# Awesome-Shield-1_0.net
KiCad netlist of a schematic drawn in EAGLE
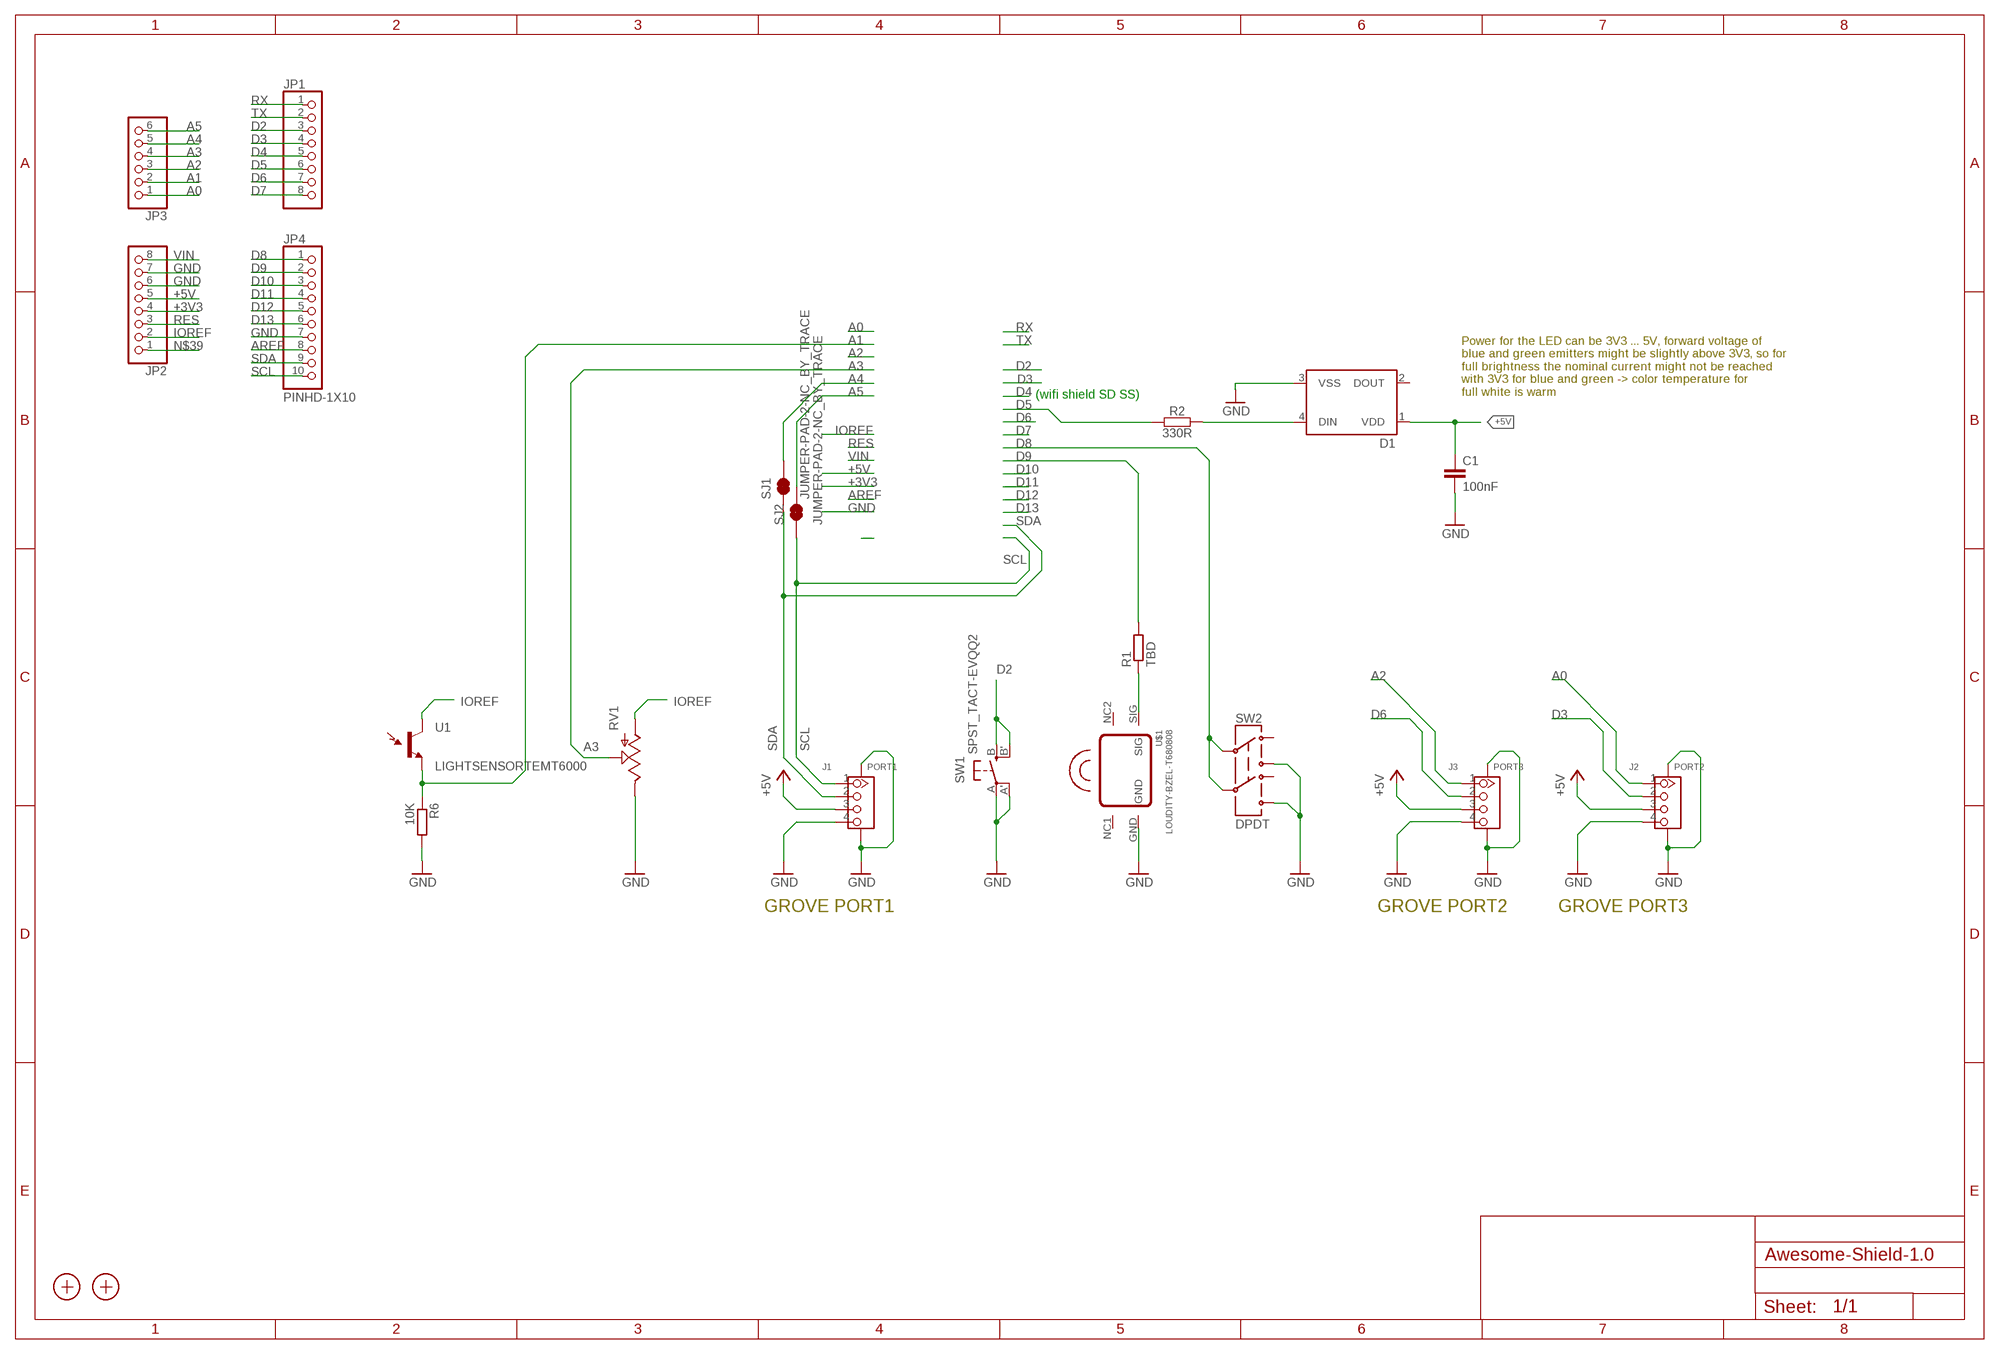
[diagram p0: schematic, sheet 1]

(export (version "E")
  (design (tool "Eeschema 10.0.6"))
  (components
    (comp (ref "C1")
      (value "100nF")
      (footprint "eagle-import:C0603")
      (libsource (lib "eagle-import") (part "C-EUC0603"))
    )
    (comp (ref "D1")
      (value "WS2812B")
      (footprint "eagle-import:WS2812B")
      (libsource (lib "eagle-import") (part "WS2812B"))
    )
    (comp (ref "J1")
      (value "PORT1")
      (footprint "eagle-import:HW4-SMD-2.0")
      (libsource (lib "eagle-import") (part "GROVE-CONNECTOR-SMD(4+2P-2.0)"))
    )
    (comp (ref "J2")
      (value "PORT2")
      (footprint "eagle-import:HW4-SMD-2.0")
      (libsource (lib "eagle-import") (part "GROVE-CONNECTOR-SMD(4+2P-2.0)"))
    )
    (comp (ref "J3")
      (value "PORT3")
      (footprint "eagle-import:HW4-SMD-2.0")
      (libsource (lib "eagle-import") (part "GROVE-CONNECTOR-SMD(4+2P-2.0)"))
    )
    (comp (ref "JP1")
      (value "PINHD-1X8CLEANBIG")
      (footprint "eagle-import:1X08-CLEANBIG")
      (libsource (lib "eagle-import") (part "PINHD-1X8CLEANBIG"))
    )
    (comp (ref "JP2")
      (value "PINHD-1X8CLEANBIG")
      (footprint "eagle-import:1X08-CLEANBIG")
      (libsource (lib "eagle-import") (part "PINHD-1X8CLEANBIG"))
    )
    (comp (ref "JP3")
      (value "PINHD-1X6CLEAN")
      (footprint "eagle-import:1X06-CLEAN")
      (libsource (lib "eagle-import") (part "PINHD-1X6CLEAN"))
    )
    (comp (ref "JP4")
      (value "PINHD-1X10")
      (footprint "eagle-import:1X10-BIG")
      (libsource (lib "eagle-import") (part "PINHD-1X10"))
    )
    (comp (ref "R1")
      (value "TBD")
      (footprint "eagle-import:R1206")
      (libsource (lib "eagle-import") (part "R-EU_R1206"))
    )
    (comp (ref "R2")
      (value "330R")
      (footprint "eagle-import:C1206")
      (libsource (lib "eagle-import") (part "RESISTOR-1206"))
    )
    (comp (ref "R6")
      (value "10K")
      (footprint "eagle-import:R1206")
      (libsource (lib "eagle-import") (part "R-EU_R1206"))
    )
    (comp (ref "RV1")
      (value "POT")
      (footprint "eagle-import:ALPS_POT")
      (libsource (lib "eagle-import") (part "POT"))
    )
    (comp (ref "SJ1")
      (value "JUMPER-PAD-2-NC_BY_TRACE")
      (footprint "eagle-import:PAD-JUMPER-2-NC_BY_TRACE_YES_SILK")
      (libsource (lib "eagle-import") (part "JUMPER-PAD-2-NC_BY_TRACE"))
    )
    (comp (ref "SJ2")
      (value "JUMPER-PAD-2-NC_BY_TRACE")
      (footprint "eagle-import:PAD-JUMPER-2-NC_BY_TRACE_YES_SILK")
      (libsource (lib "eagle-import") (part "JUMPER-PAD-2-NC_BY_TRACE"))
    )
    (comp (ref "SW1")
      (value "SPST_TACT-EVQQ2")
      (footprint "eagle-import:EVQ-Q2")
      (libsource (lib "eagle-import") (part "SPST_TACT-EVQQ2"))
    )
    (comp (ref "SW2")
      (value "DPDT")
      (footprint "eagle-import:AYZ0202")
      (libsource (lib "eagle-import") (part "SWITCH-DPDTAYZ0202"))
    )
    (comp (ref "U$1")
      (value "LOUDITY-BZEL-T680808")
      (footprint "eagle-import:SMT-68")
      (libsource (lib "eagle-import") (part "LOUDITY-BZEL-T680808"))
    )
    (comp (ref "U1")
      (value "LIGHTSENSORTEMT6000")
      (footprint "eagle-import:TEMT6000-SEN")
      (libsource (lib "eagle-import") (part "LIGHTSENSORTEMT6000"))
    )
    (comp (ref "X1")
      (value "PASSER-07")
      (footprint "eagle-import:PASSER_07MM")
      (libsource (lib "eagle-import") (part "PASSER-07"))
    )
    (comp (ref "X2")
      (value "PASSER-07")
      (footprint "eagle-import:PASSER_07MM")
      (libsource (lib "eagle-import") (part "PASSER-07"))
    )
  )
  (nets
    (net (code "1") (name "+5V") (class "Default")
      (node (ref "C1") (pin "1") (pinfunction "1_1") (pintype "passive"))
      (node (ref "D1") (pin "1") (pinfunction "VDD_1") (pintype "power_in"))
      (node (ref "J1") (pin "3") (pinfunction "3_3") (pintype "bidirectional"))
      (node (ref "J2") (pin "3") (pinfunction "3_3") (pintype "bidirectional"))
      (node (ref "J3") (pin "3") (pinfunction "3_3") (pintype "bidirectional"))
      (node (ref "JP2") (pin "5") (pinfunction "5_5") (pintype "passive"))
    )
    (net (code "2") (name "/+3V3") (class "Default")
      (node (ref "JP2") (pin "4") (pinfunction "4_4") (pintype "passive"))
    )
    (net (code "3") (name "/A0") (class "Default")
      (node (ref "J2") (pin "1") (pinfunction "1_1") (pintype "bidirectional"))
      (node (ref "JP3") (pin "1") (pinfunction "1_1") (pintype "passive"))
    )
    (net (code "4") (name "/A1") (class "Default")
      (node (ref "JP3") (pin "2") (pinfunction "2_2") (pintype "passive"))
      (node (ref "R6") (pin "1") (pinfunction "1_1") (pintype "passive"))
      (node (ref "U1") (pin "EMITTER") (pinfunction "E1_EMITTER") (pintype "passive"))
    )
    (net (code "5") (name "/A2") (class "Default")
      (node (ref "J3") (pin "1") (pinfunction "1_1") (pintype "bidirectional"))
      (node (ref "JP3") (pin "3") (pinfunction "3_3") (pintype "passive"))
    )
    (net (code "6") (name "/A3") (class "Default")
      (node (ref "JP3") (pin "4") (pinfunction "4_4") (pintype "passive"))
      (node (ref "RV1") (pin "P$2") (pinfunction "S_P$2") (pintype "passive"))
    )
    (net (code "7") (name "/A4") (class "Default")
      (node (ref "JP3") (pin "5") (pinfunction "5_5") (pintype "passive"))
      (node (ref "SJ1") (pin "2") (pinfunction "2_2") (pintype "passive"))
    )
    (net (code "8") (name "/A5") (class "Default")
      (node (ref "JP3") (pin "6") (pinfunction "6_6") (pintype "passive"))
      (node (ref "SJ2") (pin "2") (pinfunction "2_2") (pintype "passive"))
    )
    (net (code "9") (name "/AREF") (class "Default")
      (node (ref "JP4") (pin "8") (pinfunction "8_8") (pintype "passive"))
    )
    (net (code "10") (name "/D2") (class "Default")
      (node (ref "JP1") (pin "3") (pinfunction "3_3") (pintype "passive"))
      (node (ref "SW1") (pin "B") (pinfunction "S_B") (pintype "passive"))
      (node (ref "SW1") (pin "B'") (pinfunction "S1_B'") (pintype "passive"))
    )
    (net (code "11") (name "/D3") (class "Default")
      (node (ref "J2") (pin "2") (pinfunction "2_2") (pintype "bidirectional"))
      (node (ref "JP1") (pin "4") (pinfunction "4_4") (pintype "passive"))
    )
    (net (code "12") (name "/D4") (class "Default")
      (node (ref "JP1") (pin "5") (pinfunction "5_5") (pintype "passive"))
    )
    (net (code "13") (name "/D5") (class "Default")
      (node (ref "JP1") (pin "6") (pinfunction "6_6") (pintype "passive"))
      (node (ref "R2") (pin "1") (pinfunction "1_1") (pintype "passive"))
    )
    (net (code "14") (name "/D6") (class "Default")
      (node (ref "J3") (pin "2") (pinfunction "2_2") (pintype "bidirectional"))
      (node (ref "JP1") (pin "7") (pinfunction "7_7") (pintype "passive"))
    )
    (net (code "15") (name "/D7") (class "Default")
      (node (ref "JP1") (pin "8") (pinfunction "8_8") (pintype "passive"))
    )
    (net (code "16") (name "/D8") (class "Default")
      (node (ref "JP4") (pin "1") (pinfunction "1_1") (pintype "passive"))
      (node (ref "SW2") (pin "2") (pinfunction "2_2") (pintype "bidirectional"))
      (node (ref "SW2") (pin "5") (pinfunction "5_5") (pintype "bidirectional"))
    )
    (net (code "17") (name "/D9") (class "Default")
      (node (ref "JP4") (pin "2") (pinfunction "2_2") (pintype "passive"))
      (node (ref "R1") (pin "2") (pinfunction "2_2") (pintype "passive"))
    )
    (net (code "18") (name "/D10") (class "Default")
      (node (ref "JP4") (pin "3") (pinfunction "3_3") (pintype "passive"))
    )
    (net (code "19") (name "/D11") (class "Default")
      (node (ref "JP4") (pin "4") (pinfunction "4_4") (pintype "passive"))
    )
    (net (code "20") (name "/D12") (class "Default")
      (node (ref "JP4") (pin "5") (pinfunction "5_5") (pintype "passive"))
    )
    (net (code "21") (name "/D13") (class "Default")
      (node (ref "JP4") (pin "6") (pinfunction "6_6") (pintype "passive"))
    )
    (net (code "22") (name "/IOREF") (class "Default")
      (node (ref "JP2") (pin "2") (pinfunction "2_2") (pintype "passive"))
      (node (ref "RV1") (pin "P$3") (pinfunction "A_P$3") (pintype "passive"))
      (node (ref "U1") (pin "COLLECTOR") (pinfunction "C1_COLLECTOR") (pintype "passive"))
    )
    (net (code "23") (name "/N$39") (class "Default")
      (node (ref "JP2") (pin "1") (pinfunction "1_1") (pintype "passive"))
    )
    (net (code "24") (name "/RES") (class "Default")
      (node (ref "JP2") (pin "3") (pinfunction "3_3") (pintype "passive"))
    )
    (net (code "25") (name "/RX") (class "Default")
      (node (ref "JP1") (pin "1") (pinfunction "1_1") (pintype "passive"))
    )
    (net (code "26") (name "/SCL") (class "Default")
      (node (ref "J1") (pin "1") (pinfunction "1_1") (pintype "bidirectional"))
      (node (ref "JP4") (pin "10") (pinfunction "10_10") (pintype "passive"))
      (node (ref "SJ2") (pin "1") (pinfunction "1_1") (pintype "passive"))
    )
    (net (code "27") (name "/SDA") (class "Default")
      (node (ref "J1") (pin "2") (pinfunction "2_2") (pintype "bidirectional"))
      (node (ref "JP4") (pin "9") (pinfunction "9_9") (pintype "passive"))
      (node (ref "SJ1") (pin "1") (pinfunction "1_1") (pintype "passive"))
    )
    (net (code "28") (name "/TX") (class "Default")
      (node (ref "JP1") (pin "2") (pinfunction "2_2") (pintype "passive"))
    )
    (net (code "29") (name "/VIN") (class "Default")
      (node (ref "JP2") (pin "8") (pinfunction "8_8") (pintype "passive"))
    )
    (net (code "30") (name "GND") (class "Default")
      (node (ref "C1") (pin "2") (pinfunction "2_2") (pintype "passive"))
      (node (ref "D1") (pin "3") (pinfunction "VSS_3") (pintype "power_in"))
      (node (ref "J1") (pin "4") (pinfunction "4_4") (pintype "bidirectional"))
      (node (ref "J1") (pin "SS1") (pinfunction "SS1_SS1") (pintype "bidirectional"))
      (node (ref "J1") (pin "SS2") (pinfunction "SS2_SS2") (pintype "bidirectional"))
      (node (ref "J2") (pin "4") (pinfunction "4_4") (pintype "bidirectional"))
      (node (ref "J2") (pin "SS1") (pinfunction "SS1_SS1") (pintype "bidirectional"))
      (node (ref "J2") (pin "SS2") (pinfunction "SS2_SS2") (pintype "bidirectional"))
      (node (ref "J3") (pin "4") (pinfunction "4_4") (pintype "bidirectional"))
      (node (ref "J3") (pin "SS1") (pinfunction "SS1_SS1") (pintype "bidirectional"))
      (node (ref "J3") (pin "SS2") (pinfunction "SS2_SS2") (pintype "bidirectional"))
      (node (ref "JP2") (pin "6") (pinfunction "6_6") (pintype "passive"))
      (node (ref "JP2") (pin "7") (pinfunction "7_7") (pintype "passive"))
      (node (ref "JP4") (pin "7") (pinfunction "7_7") (pintype "passive"))
      (node (ref "R6") (pin "2") (pinfunction "2_2") (pintype "passive"))
      (node (ref "RV1") (pin "P$1") (pinfunction "E_P$1") (pintype "passive"))
      (node (ref "SW1") (pin "A") (pinfunction "P_A") (pintype "passive"))
      (node (ref "SW1") (pin "A'") (pinfunction "P1_A'") (pintype "passive"))
      (node (ref "SW2") (pin "3") (pinfunction "3_3") (pintype "bidirectional"))
      (node (ref "SW2") (pin "6") (pinfunction "6_6") (pintype "bidirectional"))
      (node (ref "U$1") (pin "GND") (pinfunction "GND_GND") (pintype "bidirectional"))
    )
    (net (code "31") (name "Net-(D1-DIN)") (class "Default")
      (node (ref "D1") (pin "4") (pinfunction "DIN_4") (pintype "input"))
      (node (ref "R2") (pin "2") (pinfunction "2_2") (pintype "passive"))
    )
    (net (code "32") (name "Net-(R1-Pad1)") (class "Default")
      (node (ref "R1") (pin "1") (pinfunction "1_1") (pintype "passive"))
      (node (ref "U$1") (pin "SIG") (pinfunction "SIG_SIG") (pintype "bidirectional"))
    )
    (net (code "33") (name "unconnected-(D1-DOUT-Pad2)") (class "Default")
      (node (ref "D1") (pin "2") (pinfunction "DOUT_2") (pintype "output"))
    )
    (net (code "34") (name "unconnected-(SW2-Pad1)") (class "Default")
      (node (ref "SW2") (pin "1") (pinfunction "1_1") (pintype "bidirectional"))
    )
    (net (code "35") (name "unconnected-(SW2-Pad4)") (class "Default")
      (node (ref "SW2") (pin "4") (pinfunction "4_4") (pintype "bidirectional"))
    )
    (net (code "36") (name "unconnected-(U$1-NC-PadNC1)") (class "Default")
      (node (ref "U$1") (pin "NC1") (pinfunction "NC_NC1") (pintype "bidirectional"))
    )
    (net (code "37") (name "unconnected-(U$1-NC-PadNC2)") (class "Default")
      (node (ref "U$1") (pin "NC2") (pinfunction "NC_NC2") (pintype "bidirectional"))
    )
  )
)
